# TransientsVCFG.net
KiCad netlist of a schematic drawn in EAGLE
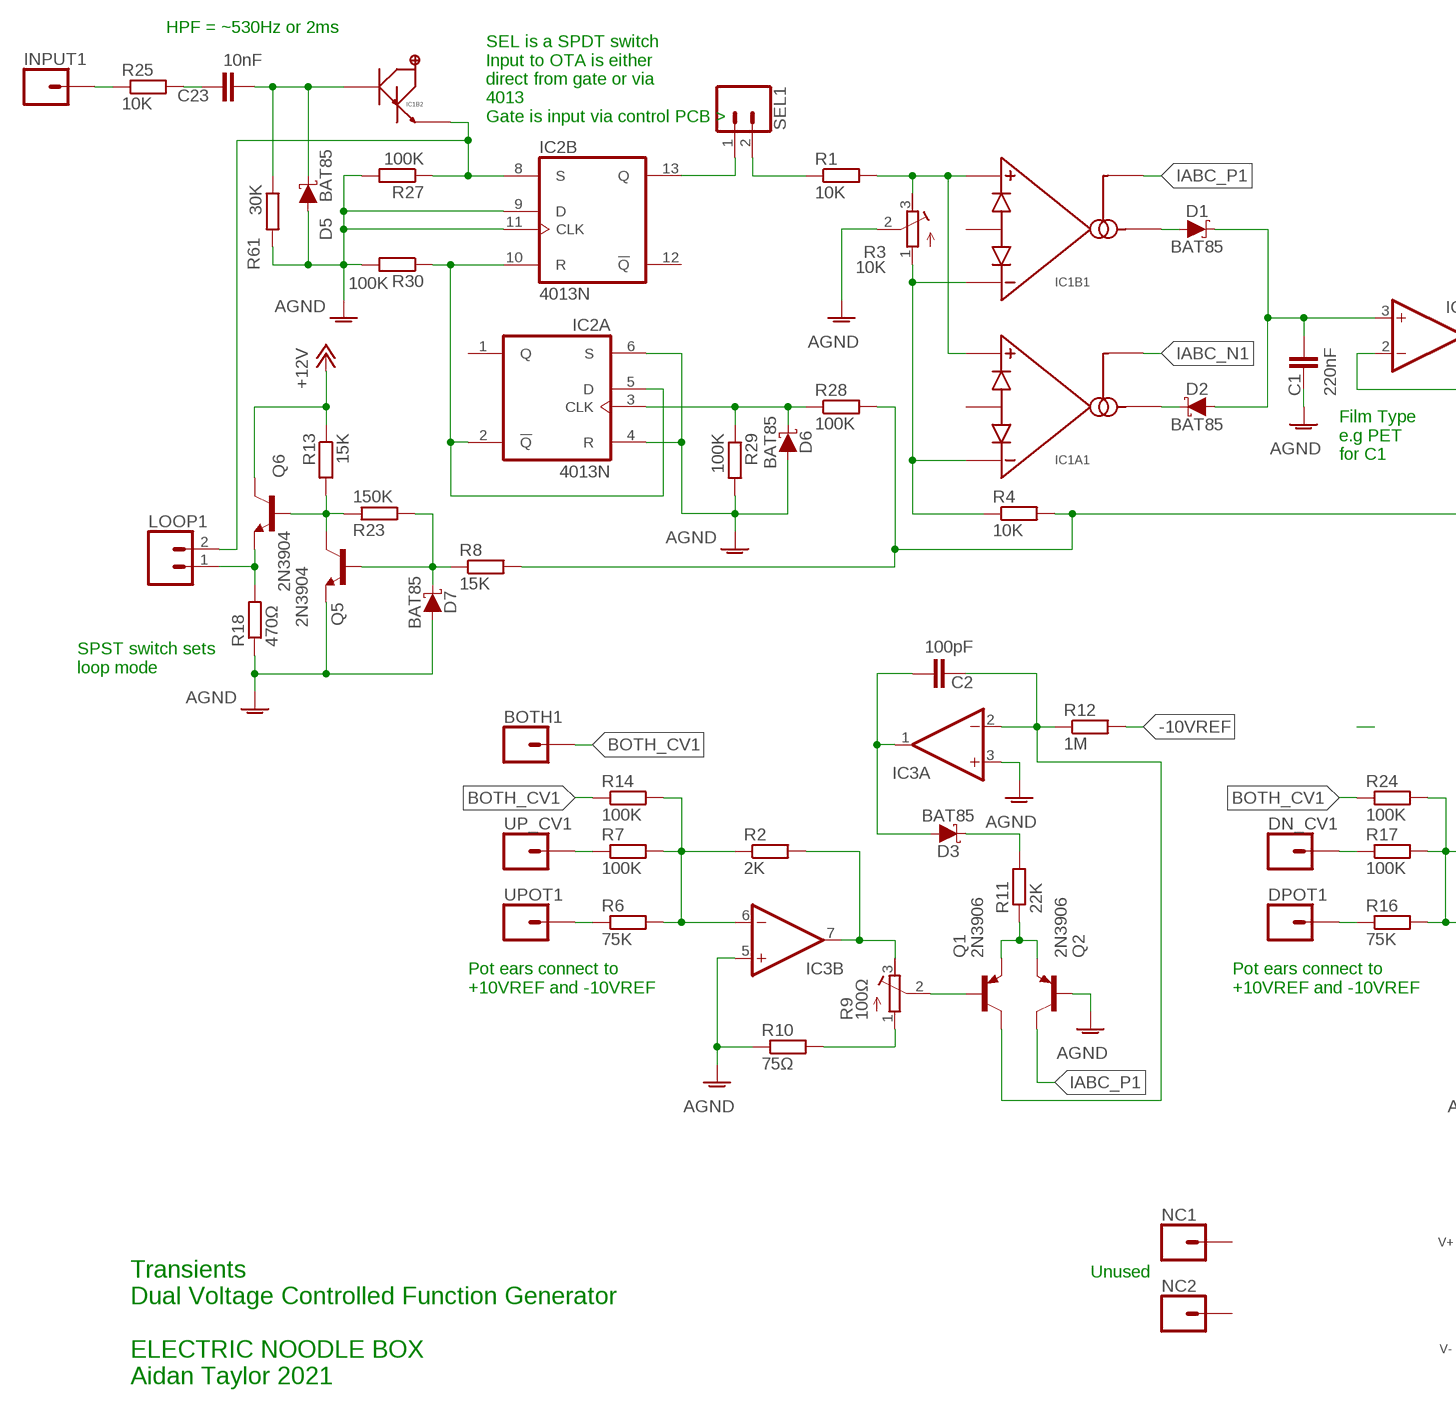
[diagram p0: schematic, sheet 1, part 1 of 2]
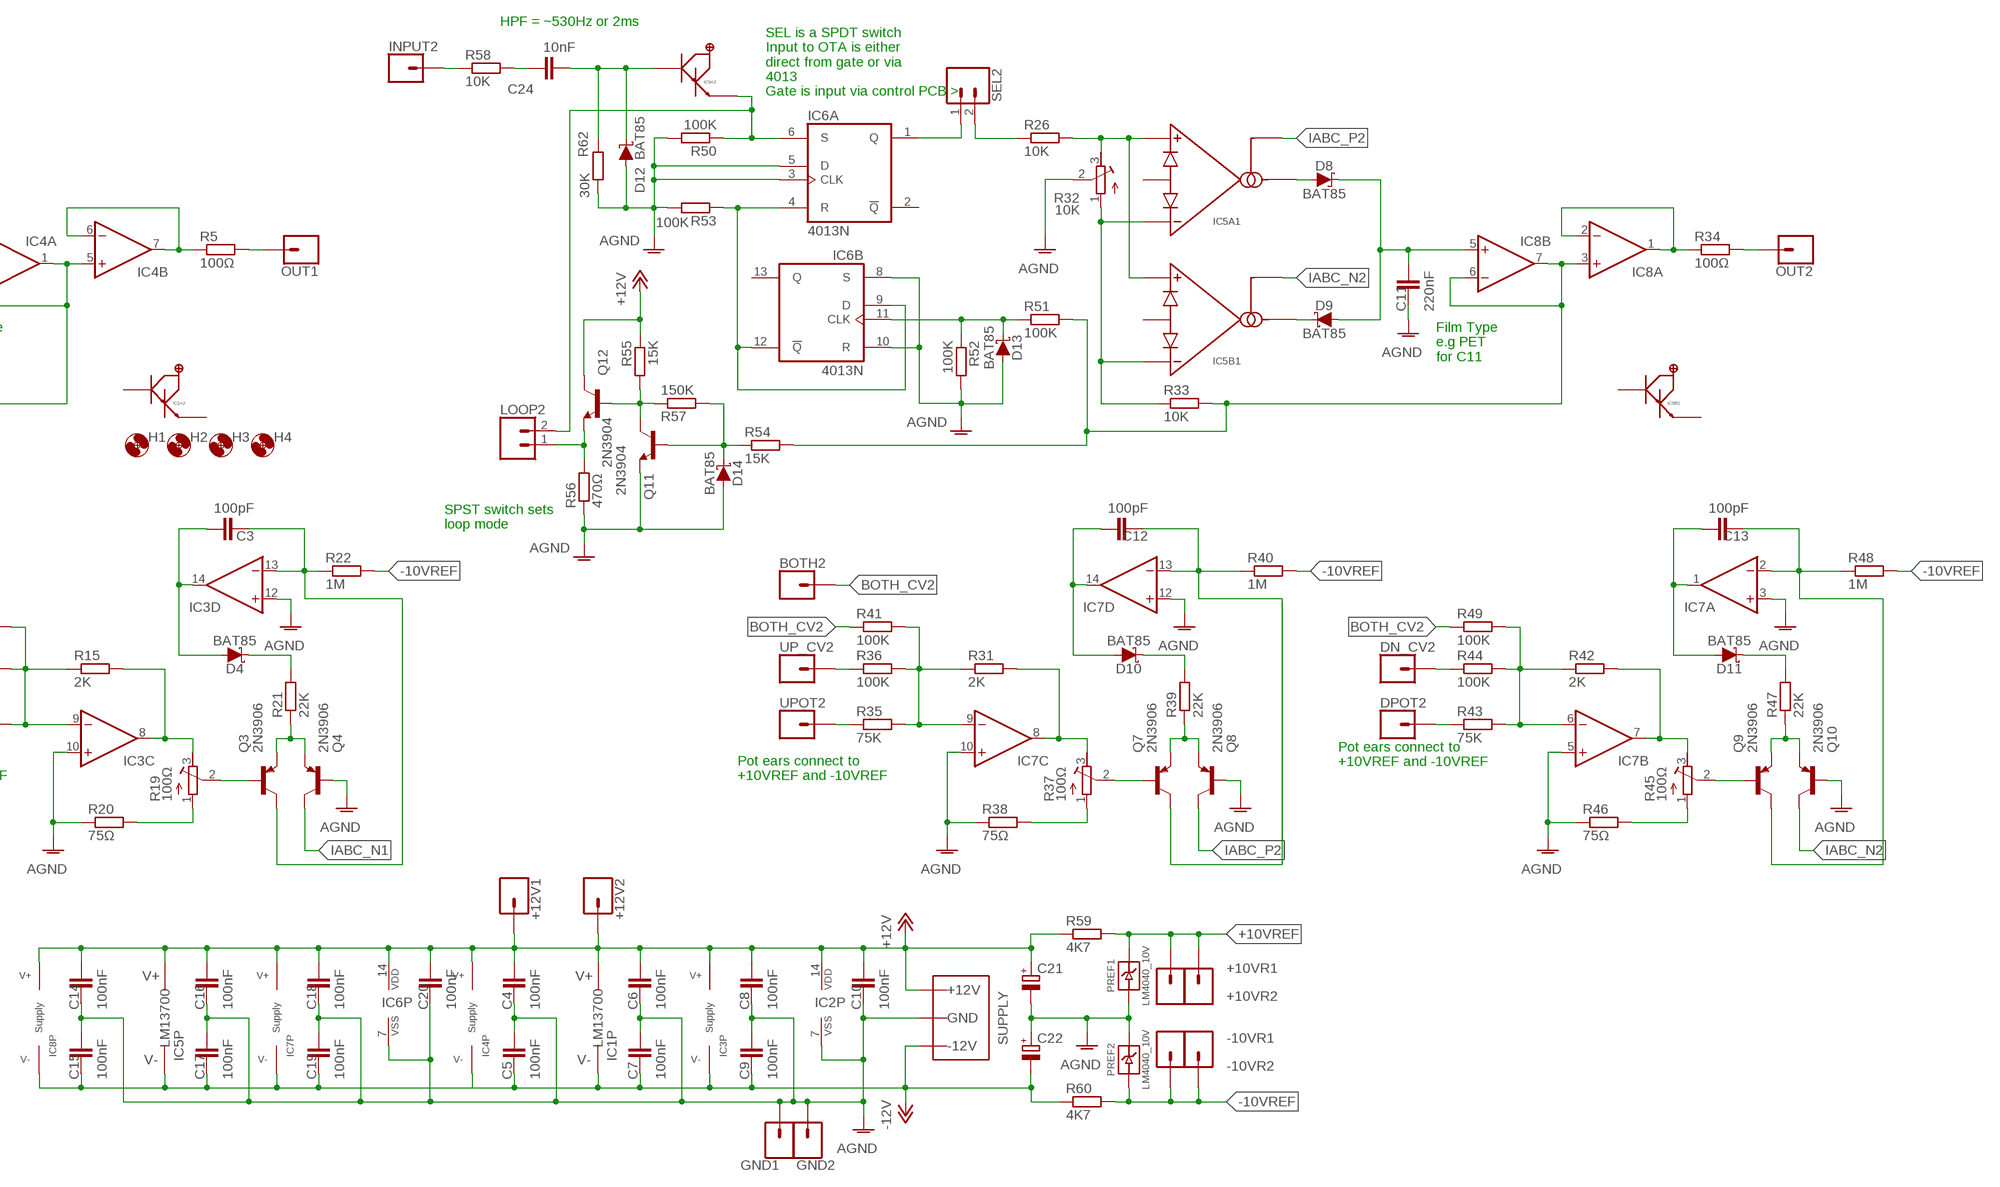
[diagram p1: schematic, sheet 1, part 2 of 2]

(export (version "E")
  (design (tool "Eeschema 10.0.6"))
  (components
    (comp (ref "+10VR1")
      (value "1XWIREPAD")
      (footprint "eagle-import:1X01")
      (libsource (lib "eagle-import") (part "1XWIREPAD"))
    )
    (comp (ref "+10VR2")
      (value "1XWIREPAD")
      (footprint "eagle-import:1X01")
      (libsource (lib "eagle-import") (part "1XWIREPAD"))
    )
    (comp (ref "+12V1")
      (value "1XWIREPAD")
      (footprint "eagle-import:1X01")
      (libsource (lib "eagle-import") (part "1XWIREPAD"))
    )
    (comp (ref "+12V2")
      (value "1XWIREPAD")
      (footprint "eagle-import:1X01")
      (libsource (lib "eagle-import") (part "1XWIREPAD"))
    )
    (comp (ref "-10VR1")
      (value "1XWIREPAD")
      (footprint "eagle-import:1X01")
      (libsource (lib "eagle-import") (part "1XWIREPAD"))
    )
    (comp (ref "-10VR2")
      (value "1XWIREPAD")
      (footprint "eagle-import:1X01")
      (libsource (lib "eagle-import") (part "1XWIREPAD"))
    )
    (comp (ref "BOTH1")
      (value "1XWIREPAD")
      (footprint "eagle-import:1X01")
      (libsource (lib "eagle-import") (part "1XWIREPAD"))
    )
    (comp (ref "BOTH2")
      (value "1XWIREPAD")
      (footprint "eagle-import:1X01")
      (libsource (lib "eagle-import") (part "1XWIREPAD"))
    )
    (comp (ref "C1")
      (value "220nF")
      (footprint "eagle-import:C050-025X075")
      (libsource (lib "eagle-import") (part "C-EU050-025X075"))
    )
    (comp (ref "C2")
      (value "100pF")
      (footprint "eagle-import:C050-025X075")
      (libsource (lib "eagle-import") (part "C-EU050-025X075"))
    )
    (comp (ref "C3")
      (value "100pF")
      (footprint "eagle-import:C050-025X075")
      (libsource (lib "eagle-import") (part "C-EU050-025X075"))
    )
    (comp (ref "C4")
      (value "100nF")
      (footprint "eagle-import:C050-025X075")
      (libsource (lib "eagle-import") (part "C-EU050-025X075"))
    )
    (comp (ref "C5")
      (value "100nF")
      (footprint "eagle-import:C050-025X075")
      (libsource (lib "eagle-import") (part "C-EU050-025X075"))
    )
    (comp (ref "C6")
      (value "100nF")
      (footprint "eagle-import:C050-025X075")
      (libsource (lib "eagle-import") (part "C-EU050-025X075"))
    )
    (comp (ref "C7")
      (value "100nF")
      (footprint "eagle-import:C050-025X075")
      (libsource (lib "eagle-import") (part "C-EU050-025X075"))
    )
    (comp (ref "C8")
      (value "100nF")
      (footprint "eagle-import:C050-025X075")
      (libsource (lib "eagle-import") (part "C-EU050-025X075"))
    )
    (comp (ref "C9")
      (value "100nF")
      (footprint "eagle-import:C050-025X075")
      (libsource (lib "eagle-import") (part "C-EU050-025X075"))
    )
    (comp (ref "C10")
      (value "100nF")
      (footprint "eagle-import:C050-025X075")
      (libsource (lib "eagle-import") (part "C-EU050-025X075"))
    )
    (comp (ref "C11")
      (value "220nF")
      (footprint "eagle-import:C050-025X075")
      (libsource (lib "eagle-import") (part "C-EU050-025X075"))
    )
    (comp (ref "C12")
      (value "100pF")
      (footprint "eagle-import:C050-025X075")
      (libsource (lib "eagle-import") (part "C-EU050-025X075"))
    )
    (comp (ref "C13")
      (value "100pF")
      (footprint "eagle-import:C050-025X075")
      (libsource (lib "eagle-import") (part "C-EU050-025X075"))
    )
    (comp (ref "C14")
      (value "100nF")
      (footprint "eagle-import:C050-025X075")
      (libsource (lib "eagle-import") (part "C-EU050-025X075"))
    )
    (comp (ref "C15")
      (value "100nF")
      (footprint "eagle-import:C050-025X075")
      (libsource (lib "eagle-import") (part "C-EU050-025X075"))
    )
    (comp (ref "C16")
      (value "100nF")
      (footprint "eagle-import:C050-025X075")
      (libsource (lib "eagle-import") (part "C-EU050-025X075"))
    )
    (comp (ref "C17")
      (value "100nF")
      (footprint "eagle-import:C050-025X075")
      (libsource (lib "eagle-import") (part "C-EU050-025X075"))
    )
    (comp (ref "C18")
      (value "100nF")
      (footprint "eagle-import:C050-025X075")
      (libsource (lib "eagle-import") (part "C-EU050-025X075"))
    )
    (comp (ref "C19")
      (value "100nF")
      (footprint "eagle-import:C050-025X075")
      (libsource (lib "eagle-import") (part "C-EU050-025X075"))
    )
    (comp (ref "C20")
      (value "100nF")
      (footprint "eagle-import:C050-025X075")
      (libsource (lib "eagle-import") (part "C-EU050-025X075"))
    )
    (comp (ref "C21")
      (value "CPOL-EUE2.5-6")
      (footprint "eagle-import:E2,5-6")
      (libsource (lib "eagle-import") (part "CPOL-EUE2.5-6"))
    )
    (comp (ref "C22")
      (value "CPOL-EUE2.5-6")
      (footprint "eagle-import:E2,5-6")
      (libsource (lib "eagle-import") (part "CPOL-EUE2.5-6"))
    )
    (comp (ref "C23")
      (value "10nF")
      (footprint "eagle-import:C050-025X075")
      (libsource (lib "eagle-import") (part "C-EU050-025X075"))
    )
    (comp (ref "C24")
      (value "10nF")
      (footprint "eagle-import:C050-025X075")
      (libsource (lib "eagle-import") (part "C-EU050-025X075"))
    )
    (comp (ref "D1")
      (value "BAT85")
      (footprint "eagle-import:DO35-7")
      (libsource (lib "eagle-import") (part "SCHOTTKY_DO35"))
    )
    (comp (ref "D2")
      (value "BAT85")
      (footprint "eagle-import:DO35-7")
      (libsource (lib "eagle-import") (part "SCHOTTKY_DO35"))
    )
    (comp (ref "D3")
      (value "BAT85")
      (footprint "eagle-import:DO35-7")
      (libsource (lib "eagle-import") (part "SCHOTTKY_DO35"))
    )
    (comp (ref "D4")
      (value "BAT85")
      (footprint "eagle-import:DO35-7")
      (libsource (lib "eagle-import") (part "SCHOTTKY_DO35"))
    )
    (comp (ref "D5")
      (value "BAT85")
      (footprint "eagle-import:DO35-7")
      (libsource (lib "eagle-import") (part "SCHOTTKY_DO35"))
    )
    (comp (ref "D6")
      (value "BAT85")
      (footprint "eagle-import:DO35-7")
      (libsource (lib "eagle-import") (part "SCHOTTKY_DO35"))
    )
    (comp (ref "D7")
      (value "BAT85")
      (footprint "eagle-import:DO35-7")
      (libsource (lib "eagle-import") (part "SCHOTTKY_DO35"))
    )
    (comp (ref "D8")
      (value "BAT85")
      (footprint "eagle-import:DO35-7")
      (libsource (lib "eagle-import") (part "SCHOTTKY_DO35"))
    )
    (comp (ref "D9")
      (value "BAT85")
      (footprint "eagle-import:DO35-7")
      (libsource (lib "eagle-import") (part "SCHOTTKY_DO35"))
    )
    (comp (ref "D10")
      (value "BAT85")
      (footprint "eagle-import:DO35-7")
      (libsource (lib "eagle-import") (part "SCHOTTKY_DO35"))
    )
    (comp (ref "D11")
      (value "BAT85")
      (footprint "eagle-import:DO35-7")
      (libsource (lib "eagle-import") (part "SCHOTTKY_DO35"))
    )
    (comp (ref "D12")
      (value "BAT85")
      (footprint "eagle-import:DO35-7")
      (libsource (lib "eagle-import") (part "SCHOTTKY_DO35"))
    )
    (comp (ref "D13")
      (value "BAT85")
      (footprint "eagle-import:DO35-7")
      (libsource (lib "eagle-import") (part "SCHOTTKY_DO35"))
    )
    (comp (ref "D14")
      (value "BAT85")
      (footprint "eagle-import:DO35-7")
      (libsource (lib "eagle-import") (part "SCHOTTKY_DO35"))
    )
    (comp (ref "DN_CV1")
      (value "1XWIREPAD")
      (footprint "eagle-import:1X01")
      (libsource (lib "eagle-import") (part "1XWIREPAD"))
    )
    (comp (ref "DN_CV2")
      (value "1XWIREPAD")
      (footprint "eagle-import:1X01")
      (libsource (lib "eagle-import") (part "1XWIREPAD"))
    )
    (comp (ref "DPOT1")
      (value "1XWIREPAD")
      (footprint "eagle-import:1X01")
      (libsource (lib "eagle-import") (part "1XWIREPAD"))
    )
    (comp (ref "DPOT2")
      (value "1XWIREPAD")
      (footprint "eagle-import:1X01")
      (libsource (lib "eagle-import") (part "1XWIREPAD"))
    )
    (comp (ref "GND1")
      (value "1XWIREPAD")
      (footprint "eagle-import:1X01")
      (libsource (lib "eagle-import") (part "1XWIREPAD"))
    )
    (comp (ref "GND2")
      (value "1XWIREPAD")
      (footprint "eagle-import:1X01")
      (libsource (lib "eagle-import") (part "1XWIREPAD"))
    )
    (comp (ref "H1")
      (value "MOUNT-HOLE3.2")
      (footprint "eagle-import:3,2")
      (libsource (lib "eagle-import") (part "MOUNT-HOLE3.2"))
    )
    (comp (ref "H2")
      (value "MOUNT-HOLE3.2")
      (footprint "eagle-import:3,2")
      (libsource (lib "eagle-import") (part "MOUNT-HOLE3.2"))
    )
    (comp (ref "H3")
      (value "MOUNT-HOLE3.2")
      (footprint "eagle-import:3,2")
      (libsource (lib "eagle-import") (part "MOUNT-HOLE3.2"))
    )
    (comp (ref "H4")
      (value "MOUNT-HOLE3.2")
      (footprint "eagle-import:3,2")
      (libsource (lib "eagle-import") (part "MOUNT-HOLE3.2"))
    )
    (comp (ref "IC1")
      (value "LM13700DIL")
      (footprint "eagle-import:DIL16")
      (libsource (lib "eagle-import") (part "LM13700DIL"))
    )
    (comp (ref "IC2")
      (value "4013N")
      (footprint "eagle-import:DIL14")
      (libsource (lib "eagle-import") (part "4013N"))
    )
    (comp (ref "IC3")
      (value "TL0X4DIL")
      (footprint "eagle-import:DIL14")
      (libsource (lib "eagle-import") (part "TL0X4DIL"))
    )
    (comp (ref "IC4")
      (value "TL0X2DIL")
      (footprint "eagle-import:DIL08")
      (libsource (lib "eagle-import") (part "TL0X2DIL"))
    )
    (comp (ref "IC5")
      (value "LM13700DIL")
      (footprint "eagle-import:DIL16")
      (libsource (lib "eagle-import") (part "LM13700DIL"))
    )
    (comp (ref "IC6")
      (value "4013N")
      (footprint "eagle-import:DIL14")
      (libsource (lib "eagle-import") (part "4013N"))
    )
    (comp (ref "IC7")
      (value "TL0X4DIL")
      (footprint "eagle-import:DIL14")
      (libsource (lib "eagle-import") (part "TL0X4DIL"))
    )
    (comp (ref "IC8")
      (value "TL0X2DIL")
      (footprint "eagle-import:DIL08")
      (libsource (lib "eagle-import") (part "TL0X2DIL"))
    )
    (comp (ref "INPUT1")
      (value "1XWIREPAD")
      (footprint "eagle-import:1X01")
      (libsource (lib "eagle-import") (part "1XWIREPAD"))
    )
    (comp (ref "INPUT2")
      (value "1XWIREPAD")
      (footprint "eagle-import:1X01")
      (libsource (lib "eagle-import") (part "1XWIREPAD"))
    )
    (comp (ref "LOOP1")
      (value "2XWIREPAD")
      (footprint "eagle-import:1X02")
      (libsource (lib "eagle-import") (part "2XWIREPAD"))
    )
    (comp (ref "LOOP2")
      (value "2XWIREPAD")
      (footprint "eagle-import:1X02")
      (libsource (lib "eagle-import") (part "2XWIREPAD"))
    )
    (comp (ref "NC1")
      (value "1XWIREPAD")
      (footprint "eagle-import:1X01")
      (libsource (lib "eagle-import") (part "1XWIREPAD"))
    )
    (comp (ref "NC2")
      (value "1XWIREPAD")
      (footprint "eagle-import:1X01")
      (libsource (lib "eagle-import") (part "1XWIREPAD"))
    )
    (comp (ref "OUT1")
      (value "1XWIREPAD")
      (footprint "eagle-import:1X01")
      (libsource (lib "eagle-import") (part "1XWIREPAD"))
    )
    (comp (ref "OUT2")
      (value "1XWIREPAD")
      (footprint "eagle-import:1X01")
      (libsource (lib "eagle-import") (part "1XWIREPAD"))
    )
    (comp (ref "PREF1")
      (value "LM4040_10V")
      (footprint "eagle-import:TO92")
      (libsource (lib "eagle-import") (part "LM4040TH"))
    )
    (comp (ref "PREF2")
      (value "LM4040_10V")
      (footprint "eagle-import:TO92")
      (libsource (lib "eagle-import") (part "LM4040TH"))
    )
    (comp (ref "Q1")
      (value "2N3906")
      (footprint "eagle-import:TO92")
      (libsource (lib "eagle-import") (part "2N3906"))
    )
    (comp (ref "Q2")
      (value "2N3906")
      (footprint "eagle-import:TO92")
      (libsource (lib "eagle-import") (part "2N3906"))
    )
    (comp (ref "Q3")
      (value "2N3906")
      (footprint "eagle-import:TO92")
      (libsource (lib "eagle-import") (part "2N3906"))
    )
    (comp (ref "Q4")
      (value "2N3906")
      (footprint "eagle-import:TO92")
      (libsource (lib "eagle-import") (part "2N3906"))
    )
    (comp (ref "Q5")
      (value "2N3904")
      (footprint "eagle-import:TO92")
      (libsource (lib "eagle-import") (part "2N3904"))
    )
    (comp (ref "Q6")
      (value "2N3904")
      (footprint "eagle-import:TO92")
      (libsource (lib "eagle-import") (part "2N3904"))
    )
    (comp (ref "Q7")
      (value "2N3906")
      (footprint "eagle-import:TO92")
      (libsource (lib "eagle-import") (part "2N3906"))
    )
    (comp (ref "Q8")
      (value "2N3906")
      (footprint "eagle-import:TO92")
      (libsource (lib "eagle-import") (part "2N3906"))
    )
    (comp (ref "Q9")
      (value "2N3906")
      (footprint "eagle-import:TO92")
      (libsource (lib "eagle-import") (part "2N3906"))
    )
    (comp (ref "Q10")
      (value "2N3906")
      (footprint "eagle-import:TO92")
      (libsource (lib "eagle-import") (part "2N3906"))
    )
    (comp (ref "Q11")
      (value "2N3904")
      (footprint "eagle-import:TO92")
      (libsource (lib "eagle-import") (part "2N3904"))
    )
    (comp (ref "Q12")
      (value "2N3904")
      (footprint "eagle-import:TO92")
      (libsource (lib "eagle-import") (part "2N3904"))
    )
    (comp (ref "R1")
      (value "10K")
      (footprint "eagle-import:0207_10")
      (libsource (lib "eagle-import") (part "R-EU_0207/10"))
    )
    (comp (ref "R2")
      (value "2K")
      (footprint "eagle-import:0207_10")
      (libsource (lib "eagle-import") (part "R-EU_0207/10"))
    )
    (comp (ref "R3")
      (value "10K")
      (footprint "eagle-import:RTRIM3296W")
      (libsource (lib "eagle-import") (part "R-TRIMM3296W"))
    )
    (comp (ref "R4")
      (value "10K")
      (footprint "eagle-import:0207_10")
      (libsource (lib "eagle-import") (part "R-EU_0207/10"))
    )
    (comp (ref "R5")
      (value "100Ω")
      (footprint "eagle-import:0207_10")
      (libsource (lib "eagle-import") (part "R-EU_0207/10"))
    )
    (comp (ref "R6")
      (value "75K")
      (footprint "eagle-import:0207_10")
      (libsource (lib "eagle-import") (part "R-EU_0207/10"))
    )
    (comp (ref "R7")
      (value "100K")
      (footprint "eagle-import:0207_10")
      (libsource (lib "eagle-import") (part "R-EU_0207/10"))
    )
    (comp (ref "R8")
      (value "15K")
      (footprint "eagle-import:0207_10")
      (libsource (lib "eagle-import") (part "R-EU_0207/10"))
    )
    (comp (ref "R9")
      (value "100Ω")
      (footprint "eagle-import:RTRIM3296W")
      (libsource (lib "eagle-import") (part "R-TRIMM3296W"))
    )
    (comp (ref "R10")
      (value "75Ω")
      (footprint "eagle-import:0207_10")
      (libsource (lib "eagle-import") (part "R-EU_0207/10"))
    )
    (comp (ref "R11")
      (value "22K")
      (footprint "eagle-import:0207_10")
      (libsource (lib "eagle-import") (part "R-EU_0207/10"))
    )
    (comp (ref "R12")
      (value "1M")
      (footprint "eagle-import:0207_10")
      (libsource (lib "eagle-import") (part "R-EU_0207/10"))
    )
    (comp (ref "R13")
      (value "15K")
      (footprint "eagle-import:0207_10")
      (libsource (lib "eagle-import") (part "R-EU_0207/10"))
    )
    (comp (ref "R14")
      (value "100K")
      (footprint "eagle-import:0207_10")
      (libsource (lib "eagle-import") (part "R-EU_0207/10"))
    )
    (comp (ref "R15")
      (value "2K")
      (footprint "eagle-import:0207_10")
      (libsource (lib "eagle-import") (part "R-EU_0207/10"))
    )
    (comp (ref "R16")
      (value "75K")
      (footprint "eagle-import:0207_10")
      (libsource (lib "eagle-import") (part "R-EU_0207/10"))
    )
    (comp (ref "R17")
      (value "100K")
      (footprint "eagle-import:0207_10")
      (libsource (lib "eagle-import") (part "R-EU_0207/10"))
    )
    (comp (ref "R18")
      (value "470Ω")
      (footprint "eagle-import:0207_10")
      (libsource (lib "eagle-import") (part "R-EU_0207/10"))
    )
    (comp (ref "R19")
      (value "100Ω")
      (footprint "eagle-import:RTRIM3296W")
      (libsource (lib "eagle-import") (part "R-TRIMM3296W"))
    )
    (comp (ref "R20")
      (value "75Ω")
      (footprint "eagle-import:0207_10")
      (libsource (lib "eagle-import") (part "R-EU_0207/10"))
    )
    (comp (ref "R21")
      (value "22K")
      (footprint "eagle-import:0207_10")
      (libsource (lib "eagle-import") (part "R-EU_0207/10"))
    )
    (comp (ref "R22")
      (value "1M")
      (footprint "eagle-import:0207_10")
      (libsource (lib "eagle-import") (part "R-EU_0207/10"))
    )
    (comp (ref "R23")
      (value "150K")
      (footprint "eagle-import:0207_10")
      (libsource (lib "eagle-import") (part "R-EU_0207/10"))
    )
    (comp (ref "R24")
      (value "100K")
      (footprint "eagle-import:0207_10")
      (libsource (lib "eagle-import") (part "R-EU_0207/10"))
    )
    (comp (ref "R25")
      (value "10K")
      (footprint "eagle-import:0207_10")
      (libsource (lib "eagle-import") (part "R-EU_0207/10"))
    )
    (comp (ref "R26")
      (value "10K")
      (footprint "eagle-import:0207_10")
      (libsource (lib "eagle-import") (part "R-EU_0207/10"))
    )
    (comp (ref "R27")
      (value "100K")
      (footprint "eagle-import:0207_10")
      (libsource (lib "eagle-import") (part "R-EU_0207/10"))
    )
    (comp (ref "R28")
      (value "100K")
      (footprint "eagle-import:0207_10")
      (libsource (lib "eagle-import") (part "R-EU_0207/10"))
    )
    (comp (ref "R29")
      (value "100K")
      (footprint "eagle-import:0207_10")
      (libsource (lib "eagle-import") (part "R-EU_0207/10"))
    )
    (comp (ref "R30")
      (value "100K")
      (footprint "eagle-import:0207_10")
      (libsource (lib "eagle-import") (part "R-EU_0207/10"))
    )
    (comp (ref "R31")
      (value "2K")
      (footprint "eagle-import:0207_10")
      (libsource (lib "eagle-import") (part "R-EU_0207/10"))
    )
    (comp (ref "R32")
      (value "10K")
      (footprint "eagle-import:RTRIM3296W")
      (libsource (lib "eagle-import") (part "R-TRIMM3296W"))
    )
    (comp (ref "R33")
      (value "10K")
      (footprint "eagle-import:0207_10")
      (libsource (lib "eagle-import") (part "R-EU_0207/10"))
    )
    (comp (ref "R34")
      (value "100Ω")
      (footprint "eagle-import:0207_10")
      (libsource (lib "eagle-import") (part "R-EU_0207/10"))
    )
    (comp (ref "R35")
      (value "75K")
      (footprint "eagle-import:0207_10")
      (libsource (lib "eagle-import") (part "R-EU_0207/10"))
    )
    (comp (ref "R36")
      (value "100K")
      (footprint "eagle-import:0207_10")
      (libsource (lib "eagle-import") (part "R-EU_0207/10"))
    )
    (comp (ref "R37")
      (value "100Ω")
      (footprint "eagle-import:RTRIM3296W")
      (libsource (lib "eagle-import") (part "R-TRIMM3296W"))
    )
    (comp (ref "R38")
      (value "75Ω")
      (footprint "eagle-import:0207_10")
      (libsource (lib "eagle-import") (part "R-EU_0207/10"))
    )
    (comp (ref "R39")
      (value "22K")
      (footprint "eagle-import:0207_10")
      (libsource (lib "eagle-import") (part "R-EU_0207/10"))
    )
    (comp (ref "R40")
      (value "1M")
      (footprint "eagle-import:0207_10")
      (libsource (lib "eagle-import") (part "R-EU_0207/10"))
    )
    (comp (ref "R41")
      (value "100K")
      (footprint "eagle-import:0207_10")
      (libsource (lib "eagle-import") (part "R-EU_0207/10"))
    )
    (comp (ref "R42")
      (value "2K")
      (footprint "eagle-import:0207_10")
      (libsource (lib "eagle-import") (part "R-EU_0207/10"))
    )
    (comp (ref "R43")
      (value "75K")
      (footprint "eagle-import:0207_10")
      (libsource (lib "eagle-import") (part "R-EU_0207/10"))
    )
    (comp (ref "R44")
      (value "100K")
      (footprint "eagle-import:0207_10")
      (libsource (lib "eagle-import") (part "R-EU_0207/10"))
    )
    (comp (ref "R45")
      (value "100Ω")
      (footprint "eagle-import:RTRIM3296W")
      (libsource (lib "eagle-import") (part "R-TRIMM3296W"))
    )
    (comp (ref "R46")
      (value "75Ω")
      (footprint "eagle-import:0207_10")
      (libsource (lib "eagle-import") (part "R-EU_0207/10"))
    )
    (comp (ref "R47")
      (value "22K")
      (footprint "eagle-import:0207_10")
      (libsource (lib "eagle-import") (part "R-EU_0207/10"))
    )
    (comp (ref "R48")
      (value "1M")
      (footprint "eagle-import:0207_10")
      (libsource (lib "eagle-import") (part "R-EU_0207/10"))
    )
    (comp (ref "R49")
      (value "100K")
      (footprint "eagle-import:0207_10")
      (libsource (lib "eagle-import") (part "R-EU_0207/10"))
    )
    (comp (ref "R50")
      (value "100K")
      (footprint "eagle-import:0207_10")
      (libsource (lib "eagle-import") (part "R-EU_0207/10"))
    )
    (comp (ref "R51")
      (value "100K")
      (footprint "eagle-import:0207_10")
      (libsource (lib "eagle-import") (part "R-EU_0207/10"))
    )
    (comp (ref "R52")
      (value "100K")
      (footprint "eagle-import:0207_10")
      (libsource (lib "eagle-import") (part "R-EU_0207/10"))
    )
    (comp (ref "R53")
      (value "100K")
      (footprint "eagle-import:0207_10")
      (libsource (lib "eagle-import") (part "R-EU_0207/10"))
    )
    (comp (ref "R54")
      (value "15K")
      (footprint "eagle-import:0207_10")
      (libsource (lib "eagle-import") (part "R-EU_0207/10"))
    )
    (comp (ref "R55")
      (value "15K")
      (footprint "eagle-import:0207_10")
      (libsource (lib "eagle-import") (part "R-EU_0207/10"))
    )
    (comp (ref "R56")
      (value "470Ω")
      (footprint "eagle-import:0207_10")
      (libsource (lib "eagle-import") (part "R-EU_0207/10"))
    )
    (comp (ref "R57")
      (value "150K")
      (footprint "eagle-import:0207_10")
      (libsource (lib "eagle-import") (part "R-EU_0207/10"))
    )
    (comp (ref "R58")
      (value "10K")
      (footprint "eagle-import:0207_10")
      (libsource (lib "eagle-import") (part "R-EU_0207/10"))
    )
    (comp (ref "R59")
      (value "4K7")
      (footprint "eagle-import:0207_10")
      (libsource (lib "eagle-import") (part "R-EU_0207/10"))
    )
    (comp (ref "R60")
      (value "4K7")
      (footprint "eagle-import:0207_10")
      (libsource (lib "eagle-import") (part "R-EU_0207/10"))
    )
    (comp (ref "R61")
      (value "30K")
      (footprint "eagle-import:0207_10")
      (libsource (lib "eagle-import") (part "R-EU_0207/10"))
    )
    (comp (ref "R62")
      (value "30K")
      (footprint "eagle-import:0207_10")
      (libsource (lib "eagle-import") (part "R-EU_0207/10"))
    )
    (comp (ref "SEL1")
      (value "2XWIREPAD")
      (footprint "eagle-import:1X02")
      (libsource (lib "eagle-import") (part "2XWIREPAD"))
    )
    (comp (ref "SEL2")
      (value "2XWIREPAD")
      (footprint "eagle-import:1X02")
      (libsource (lib "eagle-import") (part "2XWIREPAD"))
    )
    (comp (ref "UPOT1")
      (value "1XWIREPAD")
      (footprint "eagle-import:1X01")
      (libsource (lib "eagle-import") (part "1XWIREPAD"))
    )
    (comp (ref "UPOT2")
      (value "1XWIREPAD")
      (footprint "eagle-import:1X01")
      (libsource (lib "eagle-import") (part "1XWIREPAD"))
    )
    (comp (ref "UP_CV1")
      (value "1XWIREPAD")
      (footprint "eagle-import:1X01")
      (libsource (lib "eagle-import") (part "1XWIREPAD"))
    )
    (comp (ref "UP_CV2")
      (value "1XWIREPAD")
      (footprint "eagle-import:1X01")
      (libsource (lib "eagle-import") (part "1XWIREPAD"))
    )
    (comp (ref "WP1")
      (value "COMBO_SUPPLY_HEADER")
      (footprint "eagle-import:COMBINED_POWER")
      (libsource (lib "eagle-import") (part "COMBO_SUPPLY_HEADER"))
    )
  )
  (nets
    (net (code "1") (name "+10VREF") (class "Default")
      (node (ref "+10VR1") (pin "1") (pinfunction "1_1") (pintype "passive"))
      (node (ref "+10VR2") (pin "1") (pinfunction "1_1") (pintype "passive"))
      (node (ref "PREF1") (pin "2") (pinfunction "CATHODE_2") (pintype "power_in"))
      (node (ref "R59") (pin "2") (pinfunction "2_2") (pintype "passive"))
    )
    (net (code "2") (name "+12V") (class "Default")
      (node (ref "+12V1") (pin "1") (pinfunction "1_1") (pintype "passive"))
      (node (ref "+12V2") (pin "1") (pinfunction "1_1") (pintype "passive"))
      (node (ref "C10") (pin "1") (pinfunction "1_1") (pintype "passive"))
      (node (ref "C14") (pin "1") (pinfunction "1_1") (pintype "passive"))
      (node (ref "C16") (pin "1") (pinfunction "1_1") (pintype "passive"))
      (node (ref "C18") (pin "1") (pinfunction "1_1") (pintype "passive"))
      (node (ref "C20") (pin "1") (pinfunction "1_1") (pintype "passive"))
      (node (ref "C21") (pin "+") (pinfunction "+_+") (pintype "passive"))
      (node (ref "C4") (pin "1") (pinfunction "1_1") (pintype "passive"))
      (node (ref "C6") (pin "1") (pinfunction "1_1") (pintype "passive"))
      (node (ref "C8") (pin "1") (pinfunction "1_1") (pintype "passive"))
      (node (ref "IC1") (pin "11") (pinfunction "V+_11") (pintype "power_in"))
      (node (ref "IC2") (pin "14") (pinfunction "VDD_14") (pintype "power_in"))
      (node (ref "IC3") (pin "4") (pinfunction "V+_4") (pintype "bidirectional"))
      (node (ref "IC4") (pin "8") (pinfunction "V+_8") (pintype "bidirectional"))
      (node (ref "IC5") (pin "11") (pinfunction "V+_11") (pintype "power_in"))
      (node (ref "IC6") (pin "14") (pinfunction "VDD_14") (pintype "power_in"))
      (node (ref "IC7") (pin "4") (pinfunction "V+_4") (pintype "bidirectional"))
      (node (ref "IC8") (pin "8") (pinfunction "V+_8") (pintype "bidirectional"))
      (node (ref "Q12") (pin "1") (pinfunction "C_1") (pintype "passive"))
      (node (ref "Q6") (pin "1") (pinfunction "C_1") (pintype "passive"))
      (node (ref "R13") (pin "1") (pinfunction "1_1") (pintype "passive"))
      (node (ref "R55") (pin "1") (pinfunction "1_1") (pintype "passive"))
      (node (ref "R59") (pin "1") (pinfunction "1_1") (pintype "passive"))
      (node (ref "WP1") (pin "V+1") (pinfunction "V++_V+1") (pintype "power_in"))
      (node (ref "WP1") (pin "V+2") (pinfunction "V++_V+2") (pintype "power_in"))
      (node (ref "WP1") (pin "V+3") (pinfunction "V++_V+3") (pintype "power_in"))
    )
    (net (code "3") (name "-10VREF") (class "Default")
      (node (ref "-10VR1") (pin "1") (pinfunction "1_1") (pintype "passive"))
      (node (ref "-10VR2") (pin "1") (pinfunction "1_1") (pintype "passive"))
      (node (ref "PREF2") (pin "3") (pinfunction "ANODE_3") (pintype "power_in"))
      (node (ref "R12") (pin "2") (pinfunction "2_2") (pintype "passive"))
      (node (ref "R22") (pin "2") (pinfunction "2_2") (pintype "passive"))
      (node (ref "R40") (pin "2") (pinfunction "2_2") (pintype "passive"))
      (node (ref "R48") (pin "2") (pinfunction "2_2") (pintype "passive"))
      (node (ref "R60") (pin "2") (pinfunction "2_2") (pintype "passive"))
    )
    (net (code "4") (name "-12V") (class "Default")
      (node (ref "C15") (pin "2") (pinfunction "2_2") (pintype "passive"))
      (node (ref "C17") (pin "2") (pinfunction "2_2") (pintype "passive"))
      (node (ref "C19") (pin "2") (pinfunction "2_2") (pintype "passive"))
      (node (ref "C22") (pin "-") (pinfunction "-_-") (pintype "passive"))
      (node (ref "C5") (pin "2") (pinfunction "2_2") (pintype "passive"))
      (node (ref "C7") (pin "2") (pinfunction "2_2") (pintype "passive"))
      (node (ref "C9") (pin "2") (pinfunction "2_2") (pintype "passive"))
      (node (ref "IC1") (pin "6") (pinfunction "V-_6") (pintype "power_in"))
      (node (ref "IC3") (pin "11") (pinfunction "V-_11") (pintype "bidirectional"))
      (node (ref "IC4") (pin "4") (pinfunction "V-_4") (pintype "bidirectional"))
      (node (ref "IC5") (pin "6") (pinfunction "V-_6") (pintype "power_in"))
      (node (ref "IC7") (pin "11") (pinfunction "V-_11") (pintype "bidirectional"))
      (node (ref "IC8") (pin "4") (pinfunction "V-_4") (pintype "bidirectional"))
      (node (ref "R60") (pin "1") (pinfunction "1_1") (pintype "passive"))
      (node (ref "WP1") (pin "V-1") (pinfunction "V--_V-1") (pintype "power_in"))
      (node (ref "WP1") (pin "V-2") (pinfunction "V--_V-2") (pintype "power_in"))
      (node (ref "WP1") (pin "V-3") (pinfunction "V--_V-3") (pintype "power_in"))
    )
    (net (code "5") (name "AGND") (class "Default")
      (node (ref "C1") (pin "2") (pinfunction "2_2") (pintype "passive"))
      (node (ref "C10") (pin "2") (pinfunction "2_2") (pintype "passive"))
      (node (ref "C11") (pin "2") (pinfunction "2_2") (pintype "passive"))
      (node (ref "C14") (pin "2") (pinfunction "2_2") (pintype "passive"))
      (node (ref "C15") (pin "1") (pinfunction "1_1") (pintype "passive"))
      (node (ref "C16") (pin "2") (pinfunction "2_2") (pintype "passive"))
      (node (ref "C17") (pin "1") (pinfunction "1_1") (pintype "passive"))
      (node (ref "C18") (pin "2") (pinfunction "2_2") (pintype "passive"))
      (node (ref "C19") (pin "1") (pinfunction "1_1") (pintype "passive"))
      (node (ref "C20") (pin "2") (pinfunction "2_2") (pintype "passive"))
      (node (ref "C21") (pin "-") (pinfunction "-_-") (pintype "passive"))
      (node (ref "C22") (pin "+") (pinfunction "+_+") (pintype "passive"))
      (node (ref "C4") (pin "2") (pinfunction "2_2") (pintype "passive"))
      (node (ref "C5") (pin "1") (pinfunction "1_1") (pintype "passive"))
      (node (ref "C6") (pin "2") (pinfunction "2_2") (pintype "passive"))
      (node (ref "C7") (pin "1") (pinfunction "1_1") (pintype "passive"))
      (node (ref "C8") (pin "2") (pinfunction "2_2") (pintype "passive"))
      (node (ref "C9") (pin "1") (pinfunction "1_1") (pintype "passive"))
      (node (ref "D12") (pin "A") (pinfunction "A_A") (pintype "passive"))
      (node (ref "D13") (pin "A") (pinfunction "A_A") (pintype "passive"))
      (node (ref "D14") (pin "A") (pinfunction "A_A") (pintype "passive"))
      (node (ref "D5") (pin "A") (pinfunction "A_A") (pintype "passive"))
      (node (ref "D6") (pin "A") (pinfunction "A_A") (pintype "passive"))
      (node (ref "D7") (pin "A") (pinfunction "A_A") (pintype "passive"))
      (node (ref "GND1") (pin "1") (pinfunction "1_1") (pintype "passive"))
      (node (ref "GND2") (pin "1") (pinfunction "1_1") (pintype "passive"))
      (node (ref "IC2") (pin "11") (pinfunction "CLK_11") (pintype "input"))
      (node (ref "IC2") (pin "4") (pinfunction "R_4") (pintype "input"))
      (node (ref "IC2") (pin "6") (pinfunction "S_6") (pintype "input"))
      (node (ref "IC2") (pin "7") (pinfunction "VSS_7") (pintype "power_in"))
      (node (ref "IC2") (pin "9") (pinfunction "D_9") (pintype "input"))
      (node (ref "IC3") (pin "10") (pinfunction "+IN_10") (pintype "input"))
      (node (ref "IC3") (pin "12") (pinfunction "+IN_12") (pintype "input"))
      (node (ref "IC3") (pin "3") (pinfunction "+IN_3") (pintype "input"))
      (node (ref "IC3") (pin "5") (pinfunction "+IN_5") (pintype "input"))
      (node (ref "IC6") (pin "10") (pinfunction "R_10") (pintype "input"))
      (node (ref "IC6") (pin "3") (pinfunction "CLK_3") (pintype "input"))
      (node (ref "IC6") (pin "5") (pinfunction "D_5") (pintype "input"))
      (node (ref "IC6") (pin "7") (pinfunction "VSS_7") (pintype "power_in"))
      (node (ref "IC6") (pin "8") (pinfunction "S_8") (pintype "input"))
      (node (ref "IC7") (pin "10") (pinfunction "+IN_10") (pintype "input"))
      (node (ref "IC7") (pin "12") (pinfunction "+IN_12") (pintype "input"))
      (node (ref "IC7") (pin "3") (pinfunction "+IN_3") (pintype "input"))
      (node (ref "IC7") (pin "5") (pinfunction "+IN_5") (pintype "input"))
      (node (ref "PREF1") (pin "3") (pinfunction "ANODE_3") (pintype "power_in"))
      (node (ref "PREF2") (pin "2") (pinfunction "CATHODE_2") (pintype "power_in"))
      (node (ref "Q10") (pin "2") (pinfunction "B_2") (pintype "passive"))
      (node (ref "Q11") (pin "3") (pinfunction "E_3") (pintype "passive"))
      (node (ref "Q2") (pin "2") (pinfunction "B_2") (pintype "passive"))
      (node (ref "Q4") (pin "2") (pinfunction "B_2") (pintype "passive"))
      (node (ref "Q5") (pin "3") (pinfunction "E_3") (pintype "passive"))
      (node (ref "Q8") (pin "2") (pinfunction "B_2") (pintype "passive"))
      (node (ref "R10") (pin "1") (pinfunction "1_1") (pintype "passive"))
      (node (ref "R18") (pin "1") (pinfunction "1_1") (pintype "passive"))
      (node (ref "R20") (pin "1") (pinfunction "1_1") (pintype "passive"))
      (node (ref "R27") (pin "2") (pinfunction "2_2") (pintype "passive"))
      (node (ref "R29") (pin "2") (pinfunction "2_2") (pintype "passive"))
      (node (ref "R3") (pin "2") (pinfunction "S_2") (pintype "passive"))
      (node (ref "R30") (pin "2") (pinfunction "2_2") (pintype "passive"))
      (node (ref "R32") (pin "2") (pinfunction "S_2") (pintype "passive"))
      (node (ref "R38") (pin "1") (pinfunction "1_1") (pintype "passive"))
      (node (ref "R46") (pin "1") (pinfunction "1_1") (pintype "passive"))
      (node (ref "R50") (pin "2") (pinfunction "2_2") (pintype "passive"))
      (node (ref "R52") (pin "2") (pinfunction "2_2") (pintype "passive"))
      (node (ref "R53") (pin "2") (pinfunction "2_2") (pintype "passive"))
      (node (ref "R56") (pin "1") (pinfunction "1_1") (pintype "passive"))
      (node (ref "R61") (pin "2") (pinfunction "2_2") (pintype "passive"))
      (node (ref "R62") (pin "2") (pinfunction "2_2") (pintype "passive"))
      (node (ref "WP1") (pin "GND1") (pinfunction "AGND_GND1") (pintype "power_in"))
      (node (ref "WP1") (pin "GND2") (pinfunction "AGND_GND2") (pintype "power_in"))
      (node (ref "WP1") (pin "GND3") (pinfunction "AGND_GND3") (pintype "power_in"))
      (node (ref "WP1") (pin "GND4") (pinfunction "AGND_GND4") (pintype "power_in"))
      (node (ref "WP1") (pin "GND5") (pinfunction "AGND_GND5") (pintype "power_in"))
      (node (ref "WP1") (pin "GND6") (pinfunction "AGND_GND6") (pintype "power_in"))
      (node (ref "WP1") (pin "GND7") (pinfunction "AGND_GND7") (pintype "power_in"))
      (node (ref "WP1") (pin "GND8") (pinfunction "AGND_GND8") (pintype "power_in"))
    )
    (net (code "6") (name "BOTH_CV1") (class "Default")
      (node (ref "BOTH1") (pin "1") (pinfunction "1_1") (pintype "passive"))
      (node (ref "R14") (pin "1") (pinfunction "1_1") (pintype "passive"))
      (node (ref "R24") (pin "1") (pinfunction "1_1") (pintype "passive"))
    )
    (net (code "7") (name "BOTH_CV2") (class "Default")
      (node (ref "BOTH2") (pin "1") (pinfunction "1_1") (pintype "passive"))
      (node (ref "R41") (pin "1") (pinfunction "1_1") (pintype "passive"))
      (node (ref "R49") (pin "1") (pinfunction "1_1") (pintype "passive"))
    )
    (net (code "8") (name "IABC_N1") (class "Default")
      (node (ref "IC1") (pin "1") (pinfunction "AMPBIAS_1") (pintype "input"))
      (node (ref "Q4") (pin "1") (pinfunction "C_1") (pintype "passive"))
    )
    (net (code "9") (name "IABC_N2") (class "Default")
      (node (ref "IC5") (pin "16") (pinfunction "AMPBIAS_16") (pintype "input"))
      (node (ref "Q10") (pin "1") (pinfunction "C_1") (pintype "passive"))
    )
    (net (code "10") (name "IABC_P1") (class "Default")
      (node (ref "IC1") (pin "16") (pinfunction "AMPBIAS_16") (pintype "input"))
      (node (ref "Q2") (pin "1") (pinfunction "C_1") (pintype "passive"))
    )
    (net (code "11") (name "IABC_P2") (class "Default")
      (node (ref "IC5") (pin "1") (pinfunction "AMPBIAS_1") (pintype "input"))
      (node (ref "Q8") (pin "1") (pinfunction "C_1") (pintype "passive"))
    )
    (net (code "12") (name "Net-(C23-Pad1)") (class "Default")
      (node (ref "C23") (pin "1") (pinfunction "1_1") (pintype "passive"))
      (node (ref "R25") (pin "2") (pinfunction "2_2") (pintype "passive"))
    )
    (net (code "13") (name "Net-(C24-Pad1)") (class "Default")
      (node (ref "C24") (pin "1") (pinfunction "1_1") (pintype "passive"))
      (node (ref "R58") (pin "2") (pinfunction "2_2") (pintype "passive"))
    )
    (net (code "14") (name "Net-(D3-PadC)") (class "Default")
      (node (ref "D3") (pin "C") (pinfunction "C_C") (pintype "passive"))
      (node (ref "R11") (pin "2") (pinfunction "2_2") (pintype "passive"))
    )
    (net (code "15") (name "Net-(D4-PadC)") (class "Default")
      (node (ref "D4") (pin "C") (pinfunction "C_C") (pintype "passive"))
      (node (ref "R21") (pin "2") (pinfunction "2_2") (pintype "passive"))
    )
    (net (code "16") (name "Net-(D10-PadC)") (class "Default")
      (node (ref "D10") (pin "C") (pinfunction "C_C") (pintype "passive"))
      (node (ref "R39") (pin "2") (pinfunction "2_2") (pintype "passive"))
    )
    (net (code "17") (name "Net-(D11-PadC)") (class "Default")
      (node (ref "D11") (pin "C") (pinfunction "C_C") (pintype "passive"))
      (node (ref "R47") (pin "2") (pinfunction "2_2") (pintype "passive"))
    )
    (net (code "18") (name "Net-(DN_CV1-Pad1)") (class "Default")
      (node (ref "DN_CV1") (pin "1") (pinfunction "1_1") (pintype "passive"))
      (node (ref "R17") (pin "1") (pinfunction "1_1") (pintype "passive"))
    )
    (net (code "19") (name "Net-(DN_CV2-Pad1)") (class "Default")
      (node (ref "DN_CV2") (pin "1") (pinfunction "1_1") (pintype "passive"))
      (node (ref "R44") (pin "1") (pinfunction "1_1") (pintype "passive"))
    )
    (net (code "20") (name "Net-(DPOT1-Pad1)") (class "Default")
      (node (ref "DPOT1") (pin "1") (pinfunction "1_1") (pintype "passive"))
      (node (ref "R16") (pin "1") (pinfunction "1_1") (pintype "passive"))
    )
    (net (code "21") (name "Net-(DPOT2-Pad1)") (class "Default")
      (node (ref "DPOT2") (pin "1") (pinfunction "1_1") (pintype "passive"))
      (node (ref "R43") (pin "1") (pinfunction "1_1") (pintype "passive"))
    )
    (net (code "22") (name "Net-(IC1A-AMP+)") (class "Default")
      (node (ref "IC1") (pin "14") (pinfunction "AMP+_14") (pintype "input"))
      (node (ref "IC1") (pin "3") (pinfunction "AMP+_3") (pintype "input"))
      (node (ref "R1") (pin "2") (pinfunction "2_2") (pintype "passive"))
      (node (ref "R3") (pin "3") (pinfunction "E_3") (pintype "passive"))
    )
    (net (code "23") (name "Net-(IC1A-AMP-)") (class "Default")
      (node (ref "IC1") (pin "13") (pinfunction "AMP-_13") (pintype "input"))
      (node (ref "IC1") (pin "4") (pinfunction "AMP-_4") (pintype "input"))
      (node (ref "R3") (pin "1") (pinfunction "A_1") (pintype "passive"))
      (node (ref "R4") (pin "1") (pinfunction "1_1") (pintype "passive"))
    )
    (net (code "24") (name "Net-(IC1A-AMPOUT)") (class "Default")
      (node (ref "D2") (pin "C") (pinfunction "C_C") (pintype "passive"))
      (node (ref "IC1") (pin "5") (pinfunction "AMPOUT_5") (pintype "output"))
    )
    (net (code "25") (name "Net-(IC1C-AMPOUT)") (class "Default")
      (node (ref "D1") (pin "A") (pinfunction "A_A") (pintype "passive"))
      (node (ref "IC1") (pin "12") (pinfunction "AMPOUT_12") (pintype "output"))
    )
    (net (code "26") (name "Net-(IC1D-BUFF_IN)") (class "Default")
      (node (ref "C23") (pin "2") (pinfunction "2_2") (pintype "passive"))
      (node (ref "D5") (pin "C") (pinfunction "C_C") (pintype "passive"))
      (node (ref "IC1") (pin "10") (pinfunction "BUFF_IN_10") (pintype "input"))
      (node (ref "R61") (pin "1") (pinfunction "1_1") (pintype "passive"))
    )
    (net (code "27") (name "Net-(IC1D-BUFF_OUT)") (class "Default")
      (node (ref "IC1") (pin "9") (pinfunction "BUFF_OUT_9") (pintype "bidirectional"))
      (node (ref "IC2") (pin "8") (pinfunction "S_8") (pintype "input"))
      (node (ref "LOOP1") (pin "2") (pinfunction "2_2") (pintype "passive"))
      (node (ref "R27") (pin "1") (pinfunction "1_1") (pintype "passive"))
    )
    (net (code "28") (name "Net-(IC2A-CLK)") (class "Default")
      (node (ref "D6") (pin "C") (pinfunction "C_C") (pintype "passive"))
      (node (ref "IC2") (pin "3") (pinfunction "CLK_3") (pintype "input"))
      (node (ref "R28") (pin "1") (pinfunction "1_1") (pintype "passive"))
      (node (ref "R29") (pin "1") (pinfunction "1_1") (pintype "passive"))
    )
    (net (code "29") (name "Net-(IC2A-D)") (class "Default")
      (node (ref "IC2") (pin "10") (pinfunction "R_10") (pintype "input"))
      (node (ref "IC2") (pin "2") (pinfunction "~{Q}_2") (pintype "output"))
      (node (ref "IC2") (pin "5") (pinfunction "D_5") (pintype "input"))
      (node (ref "R30") (pin "1") (pinfunction "1_1") (pintype "passive"))
    )
    (net (code "30") (name "Net-(IC2B-Q)") (class "Default")
      (node (ref "IC2") (pin "13") (pinfunction "Q_13") (pintype "output"))
      (node (ref "SEL1") (pin "1") (pinfunction "1_1") (pintype "passive"))
    )
    (net (code "31") (name "Net-(IC3A--IN)") (class "Default")
      (node (ref "C2") (pin "2") (pinfunction "2_2") (pintype "passive"))
      (node (ref "IC3") (pin "2") (pinfunction "-IN_2") (pintype "input"))
      (node (ref "Q1") (pin "1") (pinfunction "C_1") (pintype "passive"))
      (node (ref "R12") (pin "1") (pinfunction "1_1") (pintype "passive"))
    )
    (net (code "32") (name "Net-(IC3A-OUT)") (class "Default")
      (node (ref "C2") (pin "1") (pinfunction "1_1") (pintype "passive"))
      (node (ref "D3") (pin "A") (pinfunction "A_A") (pintype "passive"))
      (node (ref "IC3") (pin "1") (pinfunction "OUT_1") (pintype "output"))
    )
    (net (code "33") (name "Net-(IC3B--IN)") (class "Default")
      (node (ref "IC3") (pin "6") (pinfunction "-IN_6") (pintype "input"))
      (node (ref "R14") (pin "2") (pinfunction "2_2") (pintype "passive"))
      (node (ref "R2") (pin "1") (pinfunction "1_1") (pintype "passive"))
      (node (ref "R6") (pin "2") (pinfunction "2_2") (pintype "passive"))
      (node (ref "R7") (pin "2") (pinfunction "2_2") (pintype "passive"))
    )
    (net (code "34") (name "Net-(IC3B-OUT)") (class "Default")
      (node (ref "IC3") (pin "7") (pinfunction "OUT_7") (pintype "output"))
      (node (ref "R2") (pin "2") (pinfunction "2_2") (pintype "passive"))
      (node (ref "R9") (pin "3") (pinfunction "E_3") (pintype "passive"))
    )
    (net (code "35") (name "Net-(IC3C--IN)") (class "Default")
      (node (ref "IC3") (pin "9") (pinfunction "-IN_9") (pintype "input"))
      (node (ref "R15") (pin "1") (pinfunction "1_1") (pintype "passive"))
      (node (ref "R16") (pin "2") (pinfunction "2_2") (pintype "passive"))
      (node (ref "R17") (pin "2") (pinfunction "2_2") (pintype "passive"))
      (node (ref "R24") (pin "2") (pinfunction "2_2") (pintype "passive"))
    )
    (net (code "36") (name "Net-(IC3C-OUT)") (class "Default")
      (node (ref "IC3") (pin "8") (pinfunction "OUT_8") (pintype "output"))
      (node (ref "R15") (pin "2") (pinfunction "2_2") (pintype "passive"))
      (node (ref "R19") (pin "3") (pinfunction "E_3") (pintype "passive"))
    )
    (net (code "37") (name "Net-(IC3D--IN)") (class "Default")
      (node (ref "C3") (pin "2") (pinfunction "2_2") (pintype "passive"))
      (node (ref "IC3") (pin "13") (pinfunction "-IN_13") (pintype "input"))
      (node (ref "Q3") (pin "1") (pinfunction "C_1") (pintype "passive"))
      (node (ref "R22") (pin "1") (pinfunction "1_1") (pintype "passive"))
    )
    (net (code "38") (name "Net-(IC3D-OUT)") (class "Default")
      (node (ref "C3") (pin "1") (pinfunction "1_1") (pintype "passive"))
      (node (ref "D4") (pin "A") (pinfunction "A_A") (pintype "passive"))
      (node (ref "IC3") (pin "14") (pinfunction "OUT_14") (pintype "output"))
    )
    (net (code "39") (name "Net-(IC4A-+IN)") (class "Default")
      (node (ref "C1") (pin "1") (pinfunction "1_1") (pintype "passive"))
      (node (ref "D1") (pin "C") (pinfunction "C_C") (pintype "passive"))
      (node (ref "D2") (pin "A") (pinfunction "A_A") (pintype "passive"))
      (node (ref "IC4") (pin "3") (pinfunction "+IN_3") (pintype "input"))
    )
    (net (code "40") (name "Net-(IC4A--IN)") (class "Default")
      (node (ref "IC4") (pin "1") (pinfunction "OUT_1") (pintype "output"))
      (node (ref "IC4") (pin "2") (pinfunction "-IN_2") (pintype "input"))
      (node (ref "IC4") (pin "5") (pinfunction "+IN_5") (pintype "input"))
      (node (ref "R28") (pin "2") (pinfunction "2_2") (pintype "passive"))
      (node (ref "R4") (pin "2") (pinfunction "2_2") (pintype "passive"))
      (node (ref "R8") (pin "2") (pinfunction "2_2") (pintype "passive"))
    )
    (net (code "41") (name "Net-(IC4B--IN)") (class "Default")
      (node (ref "IC4") (pin "6") (pinfunction "-IN_6") (pintype "input"))
      (node (ref "IC4") (pin "7") (pinfunction "OUT_7") (pintype "output"))
      (node (ref "R5") (pin "1") (pinfunction "1_1") (pintype "passive"))
    )
    (net (code "42") (name "Net-(IC5A-AMP+)") (class "Default")
      (node (ref "IC5") (pin "14") (pinfunction "AMP+_14") (pintype "input"))
      (node (ref "IC5") (pin "3") (pinfunction "AMP+_3") (pintype "input"))
      (node (ref "R26") (pin "2") (pinfunction "2_2") (pintype "passive"))
      (node (ref "R32") (pin "3") (pinfunction "E_3") (pintype "passive"))
    )
    (net (code "43") (name "Net-(IC5A-AMP-)") (class "Default")
      (node (ref "IC5") (pin "13") (pinfunction "AMP-_13") (pintype "input"))
      (node (ref "IC5") (pin "4") (pinfunction "AMP-_4") (pintype "input"))
      (node (ref "R32") (pin "1") (pinfunction "A_1") (pintype "passive"))
      (node (ref "R33") (pin "1") (pinfunction "1_1") (pintype "passive"))
    )
    (net (code "44") (name "Net-(IC5A-AMPOUT)") (class "Default")
      (node (ref "D8") (pin "A") (pinfunction "A_A") (pintype "passive"))
      (node (ref "IC5") (pin "5") (pinfunction "AMPOUT_5") (pintype "output"))
    )
    (net (code "45") (name "Net-(IC5B-BUFF_IN)") (class "Default")
      (node (ref "C24") (pin "2") (pinfunction "2_2") (pintype "passive"))
      (node (ref "D12") (pin "C") (pinfunction "C_C") (pintype "passive"))
      (node (ref "IC5") (pin "7") (pinfunction "BUFF_IN_7") (pintype "input"))
      (node (ref "R62") (pin "1") (pinfunction "1_1") (pintype "passive"))
    )
    (net (code "46") (name "Net-(IC5B-BUFF_OUT)") (class "Default")
      (node (ref "IC5") (pin "8") (pinfunction "BUFF_OUT_8") (pintype "bidirectional"))
      (node (ref "IC6") (pin "6") (pinfunction "S_6") (pintype "input"))
      (node (ref "LOOP2") (pin "2") (pinfunction "2_2") (pintype "passive"))
      (node (ref "R50") (pin "1") (pinfunction "1_1") (pintype "passive"))
    )
    (net (code "47") (name "Net-(IC5C-AMPOUT)") (class "Default")
      (node (ref "D9") (pin "C") (pinfunction "C_C") (pintype "passive"))
      (node (ref "IC5") (pin "12") (pinfunction "AMPOUT_12") (pintype "output"))
    )
    (net (code "48") (name "Net-(IC6A-Q)") (class "Default")
      (node (ref "IC6") (pin "1") (pinfunction "Q_1") (pintype "output"))
      (node (ref "SEL2") (pin "1") (pinfunction "1_1") (pintype "passive"))
    )
    (net (code "49") (name "Net-(IC6A-R)") (class "Default")
      (node (ref "IC6") (pin "12") (pinfunction "~{Q}_12") (pintype "output"))
      (node (ref "IC6") (pin "4") (pinfunction "R_4") (pintype "input"))
      (node (ref "IC6") (pin "9") (pinfunction "D_9") (pintype "input"))
      (node (ref "R53") (pin "1") (pinfunction "1_1") (pintype "passive"))
    )
    (net (code "50") (name "Net-(IC6B-CLK)") (class "Default")
      (node (ref "D13") (pin "C") (pinfunction "C_C") (pintype "passive"))
      (node (ref "IC6") (pin "11") (pinfunction "CLK_11") (pintype "input"))
      (node (ref "R51") (pin "1") (pinfunction "1_1") (pintype "passive"))
      (node (ref "R52") (pin "1") (pinfunction "1_1") (pintype "passive"))
    )
    (net (code "51") (name "Net-(IC7A--IN)") (class "Default")
      (node (ref "C13") (pin "2") (pinfunction "2_2") (pintype "passive"))
      (node (ref "IC7") (pin "2") (pinfunction "-IN_2") (pintype "input"))
      (node (ref "Q9") (pin "1") (pinfunction "C_1") (pintype "passive"))
      (node (ref "R48") (pin "1") (pinfunction "1_1") (pintype "passive"))
    )
    (net (code "52") (name "Net-(IC7A-OUT)") (class "Default")
      (node (ref "C13") (pin "1") (pinfunction "1_1") (pintype "passive"))
      (node (ref "D11") (pin "A") (pinfunction "A_A") (pintype "passive"))
      (node (ref "IC7") (pin "1") (pinfunction "OUT_1") (pintype "output"))
    )
    (net (code "53") (name "Net-(IC7B--IN)") (class "Default")
      (node (ref "IC7") (pin "6") (pinfunction "-IN_6") (pintype "input"))
      (node (ref "R42") (pin "1") (pinfunction "1_1") (pintype "passive"))
      (node (ref "R43") (pin "2") (pinfunction "2_2") (pintype "passive"))
      (node (ref "R44") (pin "2") (pinfunction "2_2") (pintype "passive"))
      (node (ref "R49") (pin "2") (pinfunction "2_2") (pintype "passive"))
    )
    (net (code "54") (name "Net-(IC7B-OUT)") (class "Default")
      (node (ref "IC7") (pin "7") (pinfunction "OUT_7") (pintype "output"))
      (node (ref "R42") (pin "2") (pinfunction "2_2") (pintype "passive"))
      (node (ref "R45") (pin "3") (pinfunction "E_3") (pintype "passive"))
    )
    (net (code "55") (name "Net-(IC7C--IN)") (class "Default")
      (node (ref "IC7") (pin "9") (pinfunction "-IN_9") (pintype "input"))
      (node (ref "R31") (pin "1") (pinfunction "1_1") (pintype "passive"))
      (node (ref "R35") (pin "2") (pinfunction "2_2") (pintype "passive"))
      (node (ref "R36") (pin "2") (pinfunction "2_2") (pintype "passive"))
      (node (ref "R41") (pin "2") (pinfunction "2_2") (pintype "passive"))
    )
    (net (code "56") (name "Net-(IC7C-OUT)") (class "Default")
      (node (ref "IC7") (pin "8") (pinfunction "OUT_8") (pintype "output"))
      (node (ref "R31") (pin "2") (pinfunction "2_2") (pintype "passive"))
      (node (ref "R37") (pin "3") (pinfunction "E_3") (pintype "passive"))
    )
    (net (code "57") (name "Net-(IC7D--IN)") (class "Default")
      (node (ref "C12") (pin "2") (pinfunction "2_2") (pintype "passive"))
      (node (ref "IC7") (pin "13") (pinfunction "-IN_13") (pintype "input"))
      (node (ref "Q7") (pin "1") (pinfunction "C_1") (pintype "passive"))
      (node (ref "R40") (pin "1") (pinfunction "1_1") (pintype "passive"))
    )
    (net (code "58") (name "Net-(IC7D-OUT)") (class "Default")
      (node (ref "C12") (pin "1") (pinfunction "1_1") (pintype "passive"))
      (node (ref "D10") (pin "A") (pinfunction "A_A") (pintype "passive"))
      (node (ref "IC7") (pin "14") (pinfunction "OUT_14") (pintype "output"))
    )
    (net (code "59") (name "Net-(IC8A-+IN)") (class "Default")
      (node (ref "IC8") (pin "3") (pinfunction "+IN_3") (pintype "input"))
      (node (ref "IC8") (pin "6") (pinfunction "-IN_6") (pintype "input"))
      (node (ref "IC8") (pin "7") (pinfunction "OUT_7") (pintype "output"))
      (node (ref "R33") (pin "2") (pinfunction "2_2") (pintype "passive"))
      (node (ref "R51") (pin "2") (pinfunction "2_2") (pintype "passive"))
      (node (ref "R54") (pin "2") (pinfunction "2_2") (pintype "passive"))
    )
    (net (code "60") (name "Net-(IC8A--IN)") (class "Default")
      (node (ref "IC8") (pin "1") (pinfunction "OUT_1") (pintype "output"))
      (node (ref "IC8") (pin "2") (pinfunction "-IN_2") (pintype "input"))
      (node (ref "R34") (pin "1") (pinfunction "1_1") (pintype "passive"))
    )
    (net (code "61") (name "Net-(IC8B-+IN)") (class "Default")
      (node (ref "C11") (pin "1") (pinfunction "1_1") (pintype "passive"))
      (node (ref "D8") (pin "C") (pinfunction "C_C") (pintype "passive"))
      (node (ref "D9") (pin "A") (pinfunction "A_A") (pintype "passive"))
      (node (ref "IC8") (pin "5") (pinfunction "+IN_5") (pintype "input"))
    )
    (net (code "62") (name "Net-(INPUT1-Pad1)") (class "Default")
      (node (ref "INPUT1") (pin "1") (pinfunction "1_1") (pintype "passive"))
      (node (ref "R25") (pin "1") (pinfunction "1_1") (pintype "passive"))
    )
    (net (code "63") (name "Net-(INPUT2-Pad1)") (class "Default")
      (node (ref "INPUT2") (pin "1") (pinfunction "1_1") (pintype "passive"))
      (node (ref "R58") (pin "1") (pinfunction "1_1") (pintype "passive"))
    )
    (net (code "64") (name "Net-(OUT1-Pad1)") (class "Default")
      (node (ref "OUT1") (pin "1") (pinfunction "1_1") (pintype "passive"))
      (node (ref "R5") (pin "2") (pinfunction "2_2") (pintype "passive"))
    )
    (net (code "65") (name "Net-(OUT2-Pad1)") (class "Default")
      (node (ref "OUT2") (pin "1") (pinfunction "1_1") (pintype "passive"))
      (node (ref "R34") (pin "2") (pinfunction "2_2") (pintype "passive"))
    )
    (net (code "66") (name "Net-(Q1-B)") (class "Default")
      (node (ref "Q1") (pin "2") (pinfunction "B_2") (pintype "passive"))
      (node (ref "R9") (pin "2") (pinfunction "S_2") (pintype "passive"))
    )
    (net (code "67") (name "Net-(Q1-E)") (class "Default")
      (node (ref "Q1") (pin "3") (pinfunction "E_3") (pintype "passive"))
      (node (ref "Q2") (pin "3") (pinfunction "E_3") (pintype "passive"))
      (node (ref "R11") (pin "1") (pinfunction "1_1") (pintype "passive"))
    )
    (net (code "68") (name "Net-(Q3-B)") (class "Default")
      (node (ref "Q3") (pin "2") (pinfunction "B_2") (pintype "passive"))
      (node (ref "R19") (pin "2") (pinfunction "S_2") (pintype "passive"))
    )
    (net (code "69") (name "Net-(Q3-E)") (class "Default")
      (node (ref "Q3") (pin "3") (pinfunction "E_3") (pintype "passive"))
      (node (ref "Q4") (pin "3") (pinfunction "E_3") (pintype "passive"))
      (node (ref "R21") (pin "1") (pinfunction "1_1") (pintype "passive"))
    )
    (net (code "70") (name "Net-(Q5-B)") (class "Default")
      (node (ref "D7") (pin "C") (pinfunction "C_C") (pintype "passive"))
      (node (ref "Q5") (pin "2") (pinfunction "B_2") (pintype "passive"))
      (node (ref "R23") (pin "2") (pinfunction "2_2") (pintype "passive"))
      (node (ref "R8") (pin "1") (pinfunction "1_1") (pintype "passive"))
    )
    (net (code "71") (name "Net-(Q5-C)") (class "Default")
      (node (ref "Q5") (pin "1") (pinfunction "C_1") (pintype "passive"))
      (node (ref "Q6") (pin "2") (pinfunction "B_2") (pintype "passive"))
      (node (ref "R13") (pin "2") (pinfunction "2_2") (pintype "passive"))
      (node (ref "R23") (pin "1") (pinfunction "1_1") (pintype "passive"))
    )
    (net (code "72") (name "Net-(Q6-E)") (class "Default")
      (node (ref "LOOP1") (pin "1") (pinfunction "1_1") (pintype "passive"))
      (node (ref "Q6") (pin "3") (pinfunction "E_3") (pintype "passive"))
      (node (ref "R18") (pin "2") (pinfunction "2_2") (pintype "passive"))
    )
    (net (code "73") (name "Net-(Q7-B)") (class "Default")
      (node (ref "Q7") (pin "2") (pinfunction "B_2") (pintype "passive"))
      (node (ref "R37") (pin "2") (pinfunction "S_2") (pintype "passive"))
    )
    (net (code "74") (name "Net-(Q7-E)") (class "Default")
      (node (ref "Q7") (pin "3") (pinfunction "E_3") (pintype "passive"))
      (node (ref "Q8") (pin "3") (pinfunction "E_3") (pintype "passive"))
      (node (ref "R39") (pin "1") (pinfunction "1_1") (pintype "passive"))
    )
    (net (code "75") (name "Net-(Q9-B)") (class "Default")
      (node (ref "Q9") (pin "2") (pinfunction "B_2") (pintype "passive"))
      (node (ref "R45") (pin "2") (pinfunction "S_2") (pintype "passive"))
    )
    (net (code "76") (name "Net-(Q10-E)") (class "Default")
      (node (ref "Q10") (pin "3") (pinfunction "E_3") (pintype "passive"))
      (node (ref "Q9") (pin "3") (pinfunction "E_3") (pintype "passive"))
      (node (ref "R47") (pin "1") (pinfunction "1_1") (pintype "passive"))
    )
    (net (code "77") (name "Net-(Q11-B)") (class "Default")
      (node (ref "D14") (pin "C") (pinfunction "C_C") (pintype "passive"))
      (node (ref "Q11") (pin "2") (pinfunction "B_2") (pintype "passive"))
      (node (ref "R54") (pin "1") (pinfunction "1_1") (pintype "passive"))
      (node (ref "R57") (pin "2") (pinfunction "2_2") (pintype "passive"))
    )
    (net (code "78") (name "Net-(Q11-C)") (class "Default")
      (node (ref "Q11") (pin "1") (pinfunction "C_1") (pintype "passive"))
      (node (ref "Q12") (pin "2") (pinfunction "B_2") (pintype "passive"))
      (node (ref "R55") (pin "2") (pinfunction "2_2") (pintype "passive"))
      (node (ref "R57") (pin "1") (pinfunction "1_1") (pintype "passive"))
    )
    (net (code "79") (name "Net-(Q12-E)") (class "Default")
      (node (ref "LOOP2") (pin "1") (pinfunction "1_1") (pintype "passive"))
      (node (ref "Q12") (pin "3") (pinfunction "E_3") (pintype "passive"))
      (node (ref "R56") (pin "2") (pinfunction "2_2") (pintype "passive"))
    )
    (net (code "80") (name "Net-(R1-Pad1)") (class "Default")
      (node (ref "R1") (pin "1") (pinfunction "1_1") (pintype "passive"))
      (node (ref "SEL1") (pin "2") (pinfunction "2_2") (pintype "passive"))
    )
    (net (code "81") (name "Net-(R6-Pad1)") (class "Default")
      (node (ref "R6") (pin "1") (pinfunction "1_1") (pintype "passive"))
      (node (ref "UPOT1") (pin "1") (pinfunction "1_1") (pintype "passive"))
    )
    (net (code "82") (name "Net-(R7-Pad1)") (class "Default")
      (node (ref "R7") (pin "1") (pinfunction "1_1") (pintype "passive"))
      (node (ref "UP_CV1") (pin "1") (pinfunction "1_1") (pintype "passive"))
    )
    (net (code "83") (name "Net-(R9-A)") (class "Default")
      (node (ref "R10") (pin "2") (pinfunction "2_2") (pintype "passive"))
      (node (ref "R9") (pin "1") (pinfunction "A_1") (pintype "passive"))
    )
    (net (code "84") (name "Net-(R19-A)") (class "Default")
      (node (ref "R19") (pin "1") (pinfunction "A_1") (pintype "passive"))
      (node (ref "R20") (pin "2") (pinfunction "2_2") (pintype "passive"))
    )
    (net (code "85") (name "Net-(R26-Pad1)") (class "Default")
      (node (ref "R26") (pin "1") (pinfunction "1_1") (pintype "passive"))
      (node (ref "SEL2") (pin "2") (pinfunction "2_2") (pintype "passive"))
    )
    (net (code "86") (name "Net-(R35-Pad1)") (class "Default")
      (node (ref "R35") (pin "1") (pinfunction "1_1") (pintype "passive"))
      (node (ref "UPOT2") (pin "1") (pinfunction "1_1") (pintype "passive"))
    )
    (net (code "87") (name "Net-(R36-Pad1)") (class "Default")
      (node (ref "R36") (pin "1") (pinfunction "1_1") (pintype "passive"))
      (node (ref "UP_CV2") (pin "1") (pinfunction "1_1") (pintype "passive"))
    )
    (net (code "88") (name "Net-(R37-A)") (class "Default")
      (node (ref "R37") (pin "1") (pinfunction "A_1") (pintype "passive"))
      (node (ref "R38") (pin "2") (pinfunction "2_2") (pintype "passive"))
    )
    (net (code "89") (name "Net-(R45-A)") (class "Default")
      (node (ref "R45") (pin "1") (pinfunction "A_1") (pintype "passive"))
      (node (ref "R46") (pin "2") (pinfunction "2_2") (pintype "passive"))
    )
    (net (code "90") (name "unconnected-(IC1A-DIODES-Pad2)") (class "Default")
      (node (ref "IC1") (pin "2") (pinfunction "DIODES_2") (pintype "input"))
    )
    (net (code "91") (name "unconnected-(IC1B-BUFF_IN-Pad7)") (class "Default")
      (node (ref "IC1") (pin "7") (pinfunction "BUFF_IN_7") (pintype "input"))
    )
    (net (code "92") (name "unconnected-(IC1B-BUFF_OUT-Pad8)") (class "Default")
      (node (ref "IC1") (pin "8") (pinfunction "BUFF_OUT_8") (pintype "bidirectional"))
    )
    (net (code "93") (name "unconnected-(IC1C-DIODES-Pad15)") (class "Default")
      (node (ref "IC1") (pin "15") (pinfunction "DIODES_15") (pintype "input"))
    )
    (net (code "94") (name "unconnected-(IC2A-Q-Pad1)") (class "Default")
      (node (ref "IC2") (pin "1") (pinfunction "Q_1") (pintype "output"))
    )
    (net (code "95") (name "unconnected-(IC2B-~{Q}-Pad12)") (class "Default")
      (node (ref "IC2") (pin "12") (pinfunction "~{Q}_12") (pintype "output"))
    )
    (net (code "96") (name "unconnected-(IC5A-DIODES-Pad2)") (class "Default")
      (node (ref "IC5") (pin "2") (pinfunction "DIODES_2") (pintype "input"))
    )
    (net (code "97") (name "unconnected-(IC5C-DIODES-Pad15)") (class "Default")
      (node (ref "IC5") (pin "15") (pinfunction "DIODES_15") (pintype "input"))
    )
    (net (code "98") (name "unconnected-(IC5D-BUFF_IN-Pad10)") (class "Default")
      (node (ref "IC5") (pin "10") (pinfunction "BUFF_IN_10") (pintype "input"))
    )
    (net (code "99") (name "unconnected-(IC5D-BUFF_OUT-Pad9)") (class "Default")
      (node (ref "IC5") (pin "9") (pinfunction "BUFF_OUT_9") (pintype "bidirectional"))
    )
    (net (code "100") (name "unconnected-(IC6A-~{Q}-Pad2)") (class "Default")
      (node (ref "IC6") (pin "2") (pinfunction "~{Q}_2") (pintype "output"))
    )
    (net (code "101") (name "unconnected-(IC6B-Q-Pad13)") (class "Default")
      (node (ref "IC6") (pin "13") (pinfunction "Q_13") (pintype "output"))
    )
    (net (code "102") (name "unconnected-(NC1-Pad1)") (class "Default")
      (node (ref "NC1") (pin "1") (pinfunction "1_1") (pintype "passive"))
    )
    (net (code "103") (name "unconnected-(NC2-Pad1)") (class "Default")
      (node (ref "NC2") (pin "1") (pinfunction "1_1") (pintype "passive"))
    )
  )
)
